# JFETTester.net
KiCad netlist of a schematic drawn in EAGLE
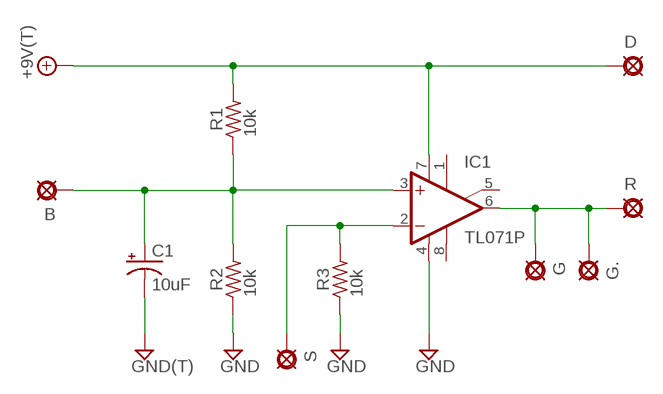
[diagram p0: schematic, sheet 1]

(export (version "E")
  (design (tool "Eeschema 10.0.6"))
  (components
    (comp (ref "+9V")
      (value "+9V(T)")
      (footprint "eagle-import:SQUARE")
      (libsource (lib "eagle-import") (part "+9V(T)"))
    )
    (comp (ref "B")
      (value "PAD")
      (footprint "eagle-import:SQUARE")
      (libsource (lib "eagle-import") (part "PAD"))
    )
    (comp (ref "C1")
      (value "10uF")
      (footprint "eagle-import:050_020_1")
      (libsource (lib "eagle-import") (part "0501"))
    )
    (comp (ref "D")
      (value "PAD")
      (footprint "eagle-import:SQUARE")
      (libsource (lib "eagle-import") (part "PAD"))
    )
    (comp (ref "G")
      (value "PAD")
      (footprint "eagle-import:SQUARE")
      (libsource (lib "eagle-import") (part "PAD"))
    )
    (comp (ref "G.")
      (value "PAD")
      (footprint "eagle-import:SQUARE")
      (libsource (lib "eagle-import") (part "PAD"))
    )
    (comp (ref "GND")
      (value "GND(T)")
      (footprint "eagle-import:SQUARE")
      (libsource (lib "eagle-import") (part "GND(T)"))
    )
    (comp (ref "IC1")
      (value "TL071P")
      (footprint "eagle-import:DIL08")
      (libsource (lib "eagle-import") (part "TL071P"))
    )
    (comp (ref "R")
      (value "PAD")
      (footprint "eagle-import:SQUARE")
      (libsource (lib "eagle-import") (part "PAD"))
    )
    (comp (ref "R1")
      (value "10k")
      (footprint "eagle-import:R0207_1V")
      (libsource (lib "eagle-import") (part "6MM.1"))
    )
    (comp (ref "R2")
      (value "10k")
      (footprint "eagle-import:R0207_1V")
      (libsource (lib "eagle-import") (part "6MM.1"))
    )
    (comp (ref "R3")
      (value "10k")
      (footprint "eagle-import:R0207_1V")
      (libsource (lib "eagle-import") (part "6MM.1"))
    )
    (comp (ref "S")
      (value "PAD")
      (footprint "eagle-import:SQUARE")
      (libsource (lib "eagle-import") (part "PAD"))
    )
  )
  (nets
    (net (code "1") (name "+9V(T)") (class "Default")
      (node (ref "+9V") (pin "1") (pinfunction "+9V_1") (pintype "power_in"))
      (node (ref "D") (pin "1") (pinfunction "PAD_1") (pintype "passive"))
      (node (ref "IC1") (pin "7") (pinfunction "V+_7") (pintype "power_in"))
      (node (ref "R1") (pin "2") (pinfunction "2_2") (pintype "passive"))
    )
    (net (code "2") (name "GND") (class "Default")
      (node (ref "C1") (pin "-") (pinfunction "-_-") (pintype "passive"))
      (node (ref "GND") (pin "1") (pinfunction "GND_1") (pintype "power_in"))
      (node (ref "IC1") (pin "4") (pinfunction "V-_4") (pintype "power_in"))
      (node (ref "R2") (pin "1") (pinfunction "1_1") (pintype "passive"))
      (node (ref "R3") (pin "1") (pinfunction "1_1") (pintype "passive"))
    )
    (net (code "3") (name "Net-(B-PAD)") (class "Default")
      (node (ref "B") (pin "1") (pinfunction "PAD_1") (pintype "passive"))
      (node (ref "C1") (pin "+") (pinfunction "+_+") (pintype "passive"))
      (node (ref "IC1") (pin "3") (pinfunction "+IN_3") (pintype "input"))
      (node (ref "R1") (pin "1") (pinfunction "1_1") (pintype "passive"))
      (node (ref "R2") (pin "2") (pinfunction "2_2") (pintype "passive"))
    )
    (net (code "4") (name "Net-(G-PAD)") (class "Default")
      (node (ref "G") (pin "1") (pinfunction "PAD_1") (pintype "passive"))
      (node (ref "G.") (pin "1") (pinfunction "PAD_1") (pintype "passive"))
      (node (ref "IC1") (pin "6") (pinfunction "OUT_6") (pintype "output"))
      (node (ref "R") (pin "1") (pinfunction "PAD_1") (pintype "passive"))
    )
    (net (code "5") (name "Net-(IC1--IN)") (class "Default")
      (node (ref "IC1") (pin "2") (pinfunction "-IN_2") (pintype "input"))
      (node (ref "R3") (pin "2") (pinfunction "2_2") (pintype "passive"))
      (node (ref "S") (pin "1") (pinfunction "PAD_1") (pintype "passive"))
    )
    (net (code "6") (name "unconnected-(IC1-ON1-Pad1)") (class "Default")
      (node (ref "IC1") (pin "1") (pinfunction "ON1_1") (pintype "passive"))
    )
    (net (code "7") (name "unconnected-(IC1-ON2-Pad5)") (class "Default")
      (node (ref "IC1") (pin "5") (pinfunction "ON2_5") (pintype "passive"))
    )
    (net (code "8") (name "unconnected-(IC1-OPT-Pad8)") (class "Default")
      (node (ref "IC1") (pin "8") (pinfunction "OPT_8") (pintype "passive"))
    )
  )
)
